# OLED_PCB_Project.net
KiCad netlist of a schematic drawn in Altium Designer
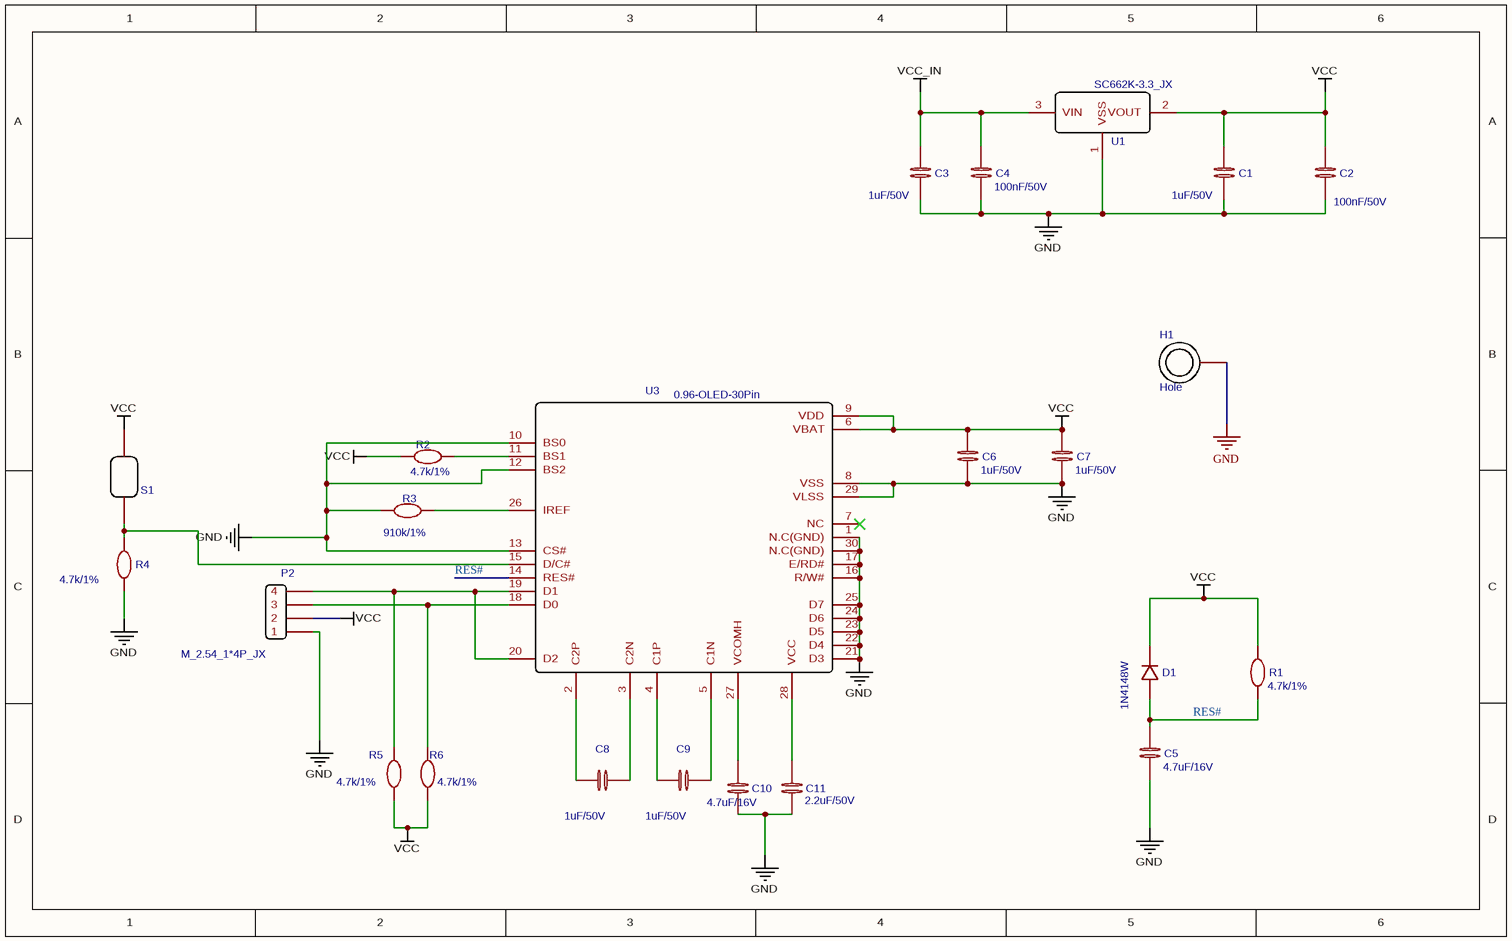
[diagram p0: OLED_PCB_Project.schdoc]

(export (version "E")
  (design (tool "Eeschema 10.0.6"))
  (components
    (comp (ref "C1") (value "1uF/50V") (footprint "0603_C_JX") (libsource (lib "") (part "1uF/50V_1")))
    (comp (ref "C2")
      (value "100nF/50V")
      (footprint "0603_C_JX")
      (libsource (lib "OLED_PCB_Project1") (part "100nF/50V"))
    )
    (comp (ref "C3") (value "1uF/50V") (footprint "0603_C_JX") (libsource (lib "") (part "1uF/50V_1")))
    (comp (ref "C4")
      (value "100nF/50V")
      (footprint "0603_C_JX")
      (libsource (lib "OLED_PCB_Project1") (part "100nF/50V"))
    )
    (comp (ref "C5") (value "4.7uF/16V") (footprint "0603_C_JX") (libsource (lib "") (part "4.7uF/16V_1")))
    (comp (ref "C6") (value "1uF/50V") (footprint "0603_C_JX") (libsource (lib "") (part "1uF/50V_1")))
    (comp (ref "C7") (value "1uF/50V") (footprint "0603_C_JX") (libsource (lib "") (part "1uF/50V_1")))
    (comp (ref "C8")
      (value "1uF/50V")
      (footprint "0603_C_JX")
      (libsource (lib "OLED_PCB_Project1") (part "1uF/50V"))
    )
    (comp (ref "C9")
      (value "1uF/50V")
      (footprint "0603_C_JX")
      (libsource (lib "OLED_PCB_Project1") (part "1uF/50V"))
    )
    (comp (ref "C10")
      (value "4.7uF/16V")
      (footprint "0603_C_JX")
      (libsource (lib "OLED_PCB_Project1") (part "4.7uF/16V"))
    )
    (comp (ref "C11")
      (value "2.2uF/50V")
      (footprint "0603_C_JX")
      (libsource (lib "OLED_PCB_Project1") (part "2.2uF/50V"))
    )
    (comp (ref "D1")
      (value "1N4148W")
      (footprint "SOD-523_JX")
      (fields (field (name "BOM_SUPPLIER PART") "C81598"))
      (libsource (lib "OLED_PCB_Project1") (part "1N4148W"))
    )
    (comp (ref "H1")
      (value "Hole")
      (footprint "PCBComponent_1 - duplicate")
      (fields (field (name "CONTRIBUTOR") "lc_ms"))
      (libsource (lib "stm32f103rc_Library") (part "Hole"))
    )
    (comp (ref "P2")
      (value "M_2.54_1*4P_JX")
      (footprint "M_2.54_1*4P_JX")
      (fields (field (name "BOM_SUPPLIER PART") "C115245") (field (name "CONTRIBUTOR") "jixin-team"))
      (libsource (lib "OLED_PCB_Project1") (part "M_2.54_1*4P_JX"))
    )
    (comp (ref "R1")
      (value "4.7k/1%")
      (footprint "0603_R_JX")
      (libsource (lib "OLED_PCB_Project1") (part "4.7k/1%"))
    )
    (comp (ref "R2")
      (value "4.7k/1%")
      (footprint "0603_R_JX")
      (libsource (lib "OLED_PCB_Project1") (part "4.7k/1%"))
    )
    (comp (ref "R3")
      (value "910k/1%")
      (footprint "0603_R_JX")
      (libsource (lib "OLED_PCB_Project1") (part "910k/1%"))
    )
    (comp (ref "R4")
      (value "4.7k/1%")
      (footprint "0603_R_JX")
      (libsource (lib "OLED_PCB_Project1") (part "4.7k/1%"))
    )
    (comp (ref "R5")
      (value "4.7k/1%")
      (footprint "0603_R_JX")
      (libsource (lib "OLED_PCB_Project1") (part "4.7k/1%"))
    )
    (comp (ref "R6")
      (value "4.7k/1%")
      (footprint "0603_R_JX")
      (libsource (lib "OLED_PCB_Project1") (part "4.7k/1%"))
    )
    (comp (ref "U1")
      (value "SC662K-3.3_JX")
      (footprint "sc662k")
      (fields (field (name "BOM_MANUFACTURER PART") "SC662K-3.3") (field (name "CONTRIBUTOR") "jixin002"))
      (libsource (lib "OLED_PCB_Project1") (part "SC662K-3.3_JX"))
    )
    (comp (ref "U3")
      (value "0.96-OLED-30Pin")
      (footprint "new_OLED30P")
      (fields (field (name "CONTRIBUTOR") "2019电子技术新讲座"))
      (libsource (lib "OLED_PCB_Project1") (part "0.96-OLED-30Pin_JX-周利杰"))
    )
    (comp (ref "U4")
      (value "S1")
      (footprint "S1")
      (fields (field (name "CONTRIBUTOR") "ywl21"))
      (libsource (lib "OLED_PCB_Project1") (part "S1"))
    )
  )
  (nets
    (net (code "1") (name "/RES#") (class "Default")
      (node (ref "C5") (pin "1") (pinfunction "1_1") (pintype "passive"))
      (node (ref "D1") (pin "2") (pinfunction "A_2") (pintype "passive"))
      (node (ref "R1") (pin "1") (pinfunction "1_1") (pintype "passive"))
      (node (ref "U3") (pin "14") (pinfunction "RES#_14") (pintype "passive"))
    )
    (net (code "2") (name "GND") (class "Default")
      (node (ref "C1") (pin "2") (pinfunction "2_2") (pintype "passive"))
      (node (ref "C10") (pin "1") (pinfunction "1_1") (pintype "passive"))
      (node (ref "C11") (pin "1") (pinfunction "1_1") (pintype "passive"))
      (node (ref "C2") (pin "2") (pinfunction "2_2") (pintype "passive"))
      (node (ref "C3") (pin "2") (pinfunction "2_2") (pintype "passive"))
      (node (ref "C4") (pin "2") (pinfunction "2_2") (pintype "passive"))
      (node (ref "C5") (pin "2") (pinfunction "2_2") (pintype "passive"))
      (node (ref "C6") (pin "2") (pinfunction "2_2") (pintype "passive"))
      (node (ref "C7") (pin "2") (pinfunction "2_2") (pintype "passive"))
      (node (ref "H1") (pin "1") (pinfunction "1_1") (pintype "passive"))
      (node (ref "P2") (pin "1") (pinfunction "1_1") (pintype "passive"))
      (node (ref "R3") (pin "1") (pinfunction "1_1") (pintype "passive"))
      (node (ref "R4") (pin "1") (pinfunction "1_1") (pintype "passive"))
      (node (ref "U1") (pin "1") (pinfunction "VSS_1") (pintype "passive"))
      (node (ref "U3") (pin "1") (pinfunction "N.C(GND)_1") (pintype "passive"))
      (node (ref "U3") (pin "10") (pinfunction "BS0_10") (pintype "passive"))
      (node (ref "U3") (pin "12") (pinfunction "BS2_12") (pintype "passive"))
      (node (ref "U3") (pin "13") (pinfunction "CS#_13") (pintype "passive"))
      (node (ref "U3") (pin "16") (pinfunction "R/W#_16") (pintype "passive"))
      (node (ref "U3") (pin "17") (pinfunction "E/RD#_17") (pintype "passive"))
      (node (ref "U3") (pin "21") (pinfunction "D3_21") (pintype "passive"))
      (node (ref "U3") (pin "22") (pinfunction "D4_22") (pintype "passive"))
      (node (ref "U3") (pin "23") (pinfunction "D5_23") (pintype "passive"))
      (node (ref "U3") (pin "24") (pinfunction "D6_24") (pintype "passive"))
      (node (ref "U3") (pin "25") (pinfunction "D7_25") (pintype "passive"))
      (node (ref "U3") (pin "29") (pinfunction "VLSS_29") (pintype "passive"))
      (node (ref "U3") (pin "30") (pinfunction "N.C(GND)_30") (pintype "passive"))
      (node (ref "U3") (pin "8") (pinfunction "VSS_8") (pintype "passive"))
    )
    (net (code "3") (name "Net-(U3-BS1)") (class "Default")
      (node (ref "R2") (pin "2") (pinfunction "2_2") (pintype "passive"))
      (node (ref "U3") (pin "11") (pinfunction "BS1_11") (pintype "passive"))
    )
    (net (code "4") (name "Net-(U3-C1N)") (class "Default")
      (node (ref "C9") (pin "2") (pinfunction "2_2") (pintype "passive"))
      (node (ref "U3") (pin "5") (pinfunction "C1N_5") (pintype "passive"))
    )
    (net (code "5") (name "Net-(U3-C1P)") (class "Default")
      (node (ref "C9") (pin "1") (pinfunction "1_1") (pintype "passive"))
      (node (ref "U3") (pin "4") (pinfunction "C1P_4") (pintype "passive"))
    )
    (net (code "6") (name "Net-(U3-C2N)") (class "Default")
      (node (ref "C8") (pin "2") (pinfunction "2_2") (pintype "passive"))
      (node (ref "U3") (pin "3") (pinfunction "C2N_3") (pintype "passive"))
    )
    (net (code "7") (name "Net-(U3-C2P)") (class "Default")
      (node (ref "C8") (pin "1") (pinfunction "1_1") (pintype "passive"))
      (node (ref "U3") (pin "2") (pinfunction "C2P_2") (pintype "passive"))
    )
    (net (code "8") (name "Net-(U3-D0)") (class "Default")
      (node (ref "P2") (pin "3") (pinfunction "3_3") (pintype "passive"))
      (node (ref "R6") (pin "2") (pinfunction "2_2") (pintype "passive"))
      (node (ref "U3") (pin "18") (pinfunction "D0_18") (pintype "passive"))
    )
    (net (code "9") (name "Net-(U3-D1)") (class "Default")
      (node (ref "P2") (pin "4") (pinfunction "4_4") (pintype "passive"))
      (node (ref "R5") (pin "2") (pinfunction "2_2") (pintype "passive"))
      (node (ref "U3") (pin "19") (pinfunction "D1_19") (pintype "passive"))
      (node (ref "U3") (pin "20") (pinfunction "D2_20") (pintype "passive"))
    )
    (net (code "10") (name "Net-(U3-D{slash}C#)") (class "Default")
      (node (ref "R4") (pin "2") (pinfunction "2_2") (pintype "passive"))
      (node (ref "U3") (pin "15") (pinfunction "D/C#_15") (pintype "passive"))
      (node (ref "U4") (pin "2") (pinfunction "2_2") (pintype "passive"))
    )
    (net (code "11") (name "Net-(U3-IREF)") (class "Default")
      (node (ref "R3") (pin "2") (pinfunction "2_2") (pintype "passive"))
      (node (ref "U3") (pin "26") (pinfunction "IREF_26") (pintype "passive"))
    )
    (net (code "12") (name "Net-(U3-VCC)") (class "Default")
      (node (ref "C11") (pin "2") (pinfunction "2_2") (pintype "passive"))
      (node (ref "U3") (pin "28") (pinfunction "VCC_28") (pintype "passive"))
    )
    (net (code "13") (name "Net-(U3-VCOMH)") (class "Default")
      (node (ref "C10") (pin "2") (pinfunction "2_2") (pintype "passive"))
      (node (ref "U3") (pin "27") (pinfunction "VCOMH_27") (pintype "passive"))
    )
    (net (code "14") (name "VCC") (class "Default")
      (node (ref "C1") (pin "1") (pinfunction "1_1") (pintype "passive"))
      (node (ref "C2") (pin "1") (pinfunction "1_1") (pintype "passive"))
      (node (ref "C6") (pin "1") (pinfunction "1_1") (pintype "passive"))
      (node (ref "C7") (pin "1") (pinfunction "1_1") (pintype "passive"))
      (node (ref "D1") (pin "1") (pinfunction "K_1") (pintype "passive"))
      (node (ref "P2") (pin "2") (pinfunction "2_2") (pintype "passive"))
      (node (ref "R1") (pin "2") (pinfunction "2_2") (pintype "passive"))
      (node (ref "R2") (pin "1") (pinfunction "1_1") (pintype "passive"))
      (node (ref "R5") (pin "1") (pinfunction "1_1") (pintype "passive"))
      (node (ref "R6") (pin "1") (pinfunction "1_1") (pintype "passive"))
      (node (ref "U1") (pin "2") (pinfunction "VOUT_2") (pintype "passive"))
      (node (ref "U3") (pin "6") (pinfunction "VBAT_6") (pintype "passive"))
      (node (ref "U3") (pin "9") (pinfunction "VDD_9") (pintype "passive"))
      (node (ref "U4") (pin "1") (pinfunction "1_1") (pintype "passive"))
    )
    (net (code "15") (name "VCC_IN") (class "Default")
      (node (ref "C3") (pin "1") (pinfunction "1_1") (pintype "passive"))
      (node (ref "C4") (pin "1") (pinfunction "1_1") (pintype "passive"))
      (node (ref "U1") (pin "3") (pinfunction "VIN_3") (pintype "passive"))
    )
    (net (code "16") (name "unconnected-(U3-NC-Pad7)") (class "Default")
      (node (ref "U3") (pin "7") (pinfunction "NC_7") (pintype "passive+no_connect"))
    )
  )
)
